# GSMGPSShield.net
KiCad netlist of a schematic drawn in EAGLE
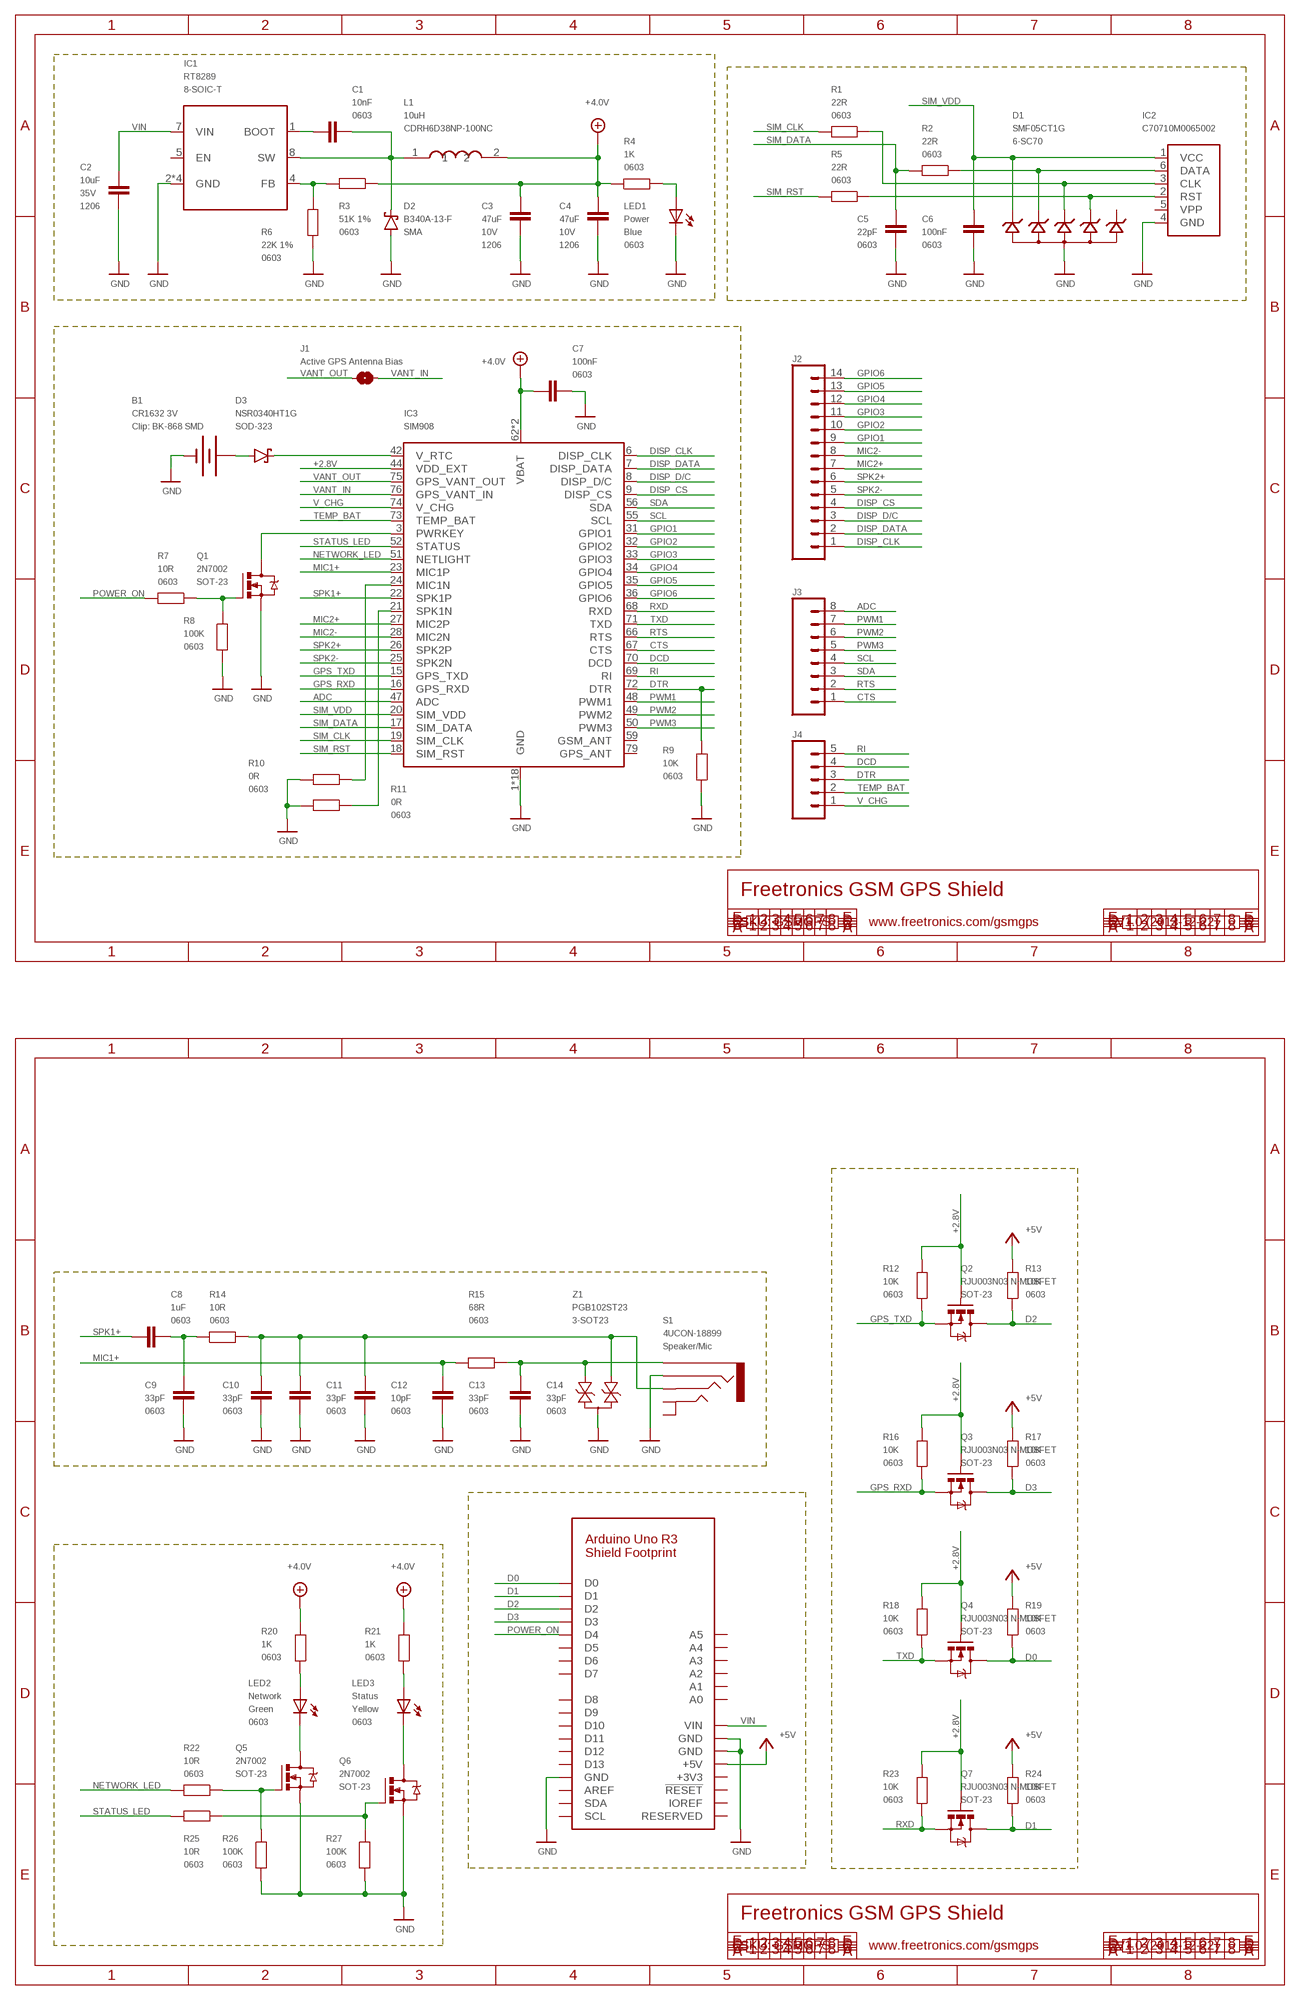
[diagram p0: schematic, sheet 1]

(export (version "E")
  (design (tool "Eeschema 10.0.6"))
  (components
    (comp (ref "B1")
      (value "CR1632 3V")
      (footprint "eagle-import:BATCON_16MM")
      (fields (field (name "FOO") "Clip: BK-868 SMD"))
      (libsource (lib "eagle-import") (part "BATTERY"))
    )
    (comp (ref "C1")
      (value "10nF")
      (footprint "eagle-import:0603")
      (fields (field (name "PACKAGE") "0603"))
      (libsource (lib "eagle-import") (part "CAP0603"))
    )
    (comp (ref "C2")
      (value "10uF")
      (footprint "eagle-import:C1206")
      (fields (field (name "PACKAGE") "1206") (field (name "VOLTAGE") "35V"))
      (libsource (lib "eagle-import") (part "C-EUC1206"))
    )
    (comp (ref "C3")
      (value "47uF")
      (footprint "eagle-import:C1206")
      (fields (field (name "PACKAGE") "1206") (field (name "VOLTAGE") "10V"))
      (libsource (lib "eagle-import") (part "C-EUC1206"))
    )
    (comp (ref "C4")
      (value "47uF")
      (footprint "eagle-import:C1206")
      (fields (field (name "PACKAGE") "1206") (field (name "VOLTAGE") "10V"))
      (libsource (lib "eagle-import") (part "C-EUC1206"))
    )
    (comp (ref "C5")
      (value "22pF")
      (footprint "eagle-import:0603")
      (fields (field (name "PACKAGE") "0603"))
      (libsource (lib "eagle-import") (part "CAP0603"))
    )
    (comp (ref "C6")
      (value "100nF")
      (footprint "eagle-import:0603")
      (fields (field (name "PACKAGE") "0603"))
      (libsource (lib "eagle-import") (part "CAP0603"))
    )
    (comp (ref "C7")
      (value "100nF")
      (footprint "eagle-import:0603")
      (fields (field (name "PACKAGE") "0603"))
      (libsource (lib "eagle-import") (part "CAP0603"))
    )
    (comp (ref "C8")
      (value "1uF")
      (footprint "eagle-import:0603")
      (fields (field (name "PACKAGE") "0603"))
      (libsource (lib "eagle-import") (part "CAP0603"))
    )
    (comp (ref "C9")
      (value "33pF")
      (footprint "eagle-import:0603")
      (fields (field (name "PACKAGE") "0603"))
      (libsource (lib "eagle-import") (part "CAP0603"))
    )
    (comp (ref "C10")
      (value "33pF")
      (footprint "eagle-import:0603")
      (fields (field (name "PACKAGE") "0603"))
      (libsource (lib "eagle-import") (part "CAP0603"))
    )
    (comp (ref "C11")
      (value "33pF")
      (footprint "eagle-import:0603")
      (fields (field (name "PACKAGE") "0603"))
      (libsource (lib "eagle-import") (part "CAP0603"))
    )
    (comp (ref "C12")
      (value "10pF")
      (footprint "eagle-import:0603")
      (fields (field (name "PACKAGE") "0603"))
      (libsource (lib "eagle-import") (part "CAP0603"))
    )
    (comp (ref "C13")
      (value "33pF")
      (footprint "eagle-import:0603")
      (fields (field (name "PACKAGE") "0603"))
      (libsource (lib "eagle-import") (part "CAP0603"))
    )
    (comp (ref "C14")
      (value "33pF")
      (footprint "eagle-import:0603")
      (fields (field (name "PACKAGE") "0603"))
      (libsource (lib "eagle-import") (part "CAP0603"))
    )
    (comp (ref "D1")
      (value "SMF05CT1G")
      (footprint "eagle-import:SC70-6")
      (fields (field (name "PACKAGE") "6-SC70"))
      (libsource (lib "eagle-import") (part "SMF05CT1G"))
    )
    (comp (ref "D2")
      (value "B340A-13-F")
      (footprint "eagle-import:SMA")
      (fields (field (name "PACKAGE") "SMA"))
      (libsource (lib "eagle-import") (part "SCHOTTKY-SMA"))
    )
    (comp (ref "D3")
      (value "NSR0340HT1G")
      (footprint "eagle-import:SOD-323")
      (fields (field (name "PACKAGE") "SOD-323"))
      (libsource (lib "eagle-import") (part "SCHOTTKY-SOD323"))
    )
    (comp (ref "IC1")
      (value "RT8289")
      (footprint "eagle-import:SO08T")
      (fields (field (name "PACKAGE") "8-SOIC-T"))
      (libsource (lib "eagle-import") (part "RT8289"))
    )
    (comp (ref "IC2")
      (value "C70710M0065002")
      (footprint "eagle-import:C70710M0065002")
      (libsource (lib "eagle-import") (part "C70710M0065002"))
    )
    (comp (ref "IC3")
      (value "SIM908")
      (footprint "eagle-import:SIM908")
      (libsource (lib "eagle-import") (part "SIM908"))
    )
    (comp (ref "J1")
      (value "Active GPS Antenna Bias")
      (footprint "eagle-import:SJ")
      (libsource (lib "eagle-import") (part "SJ"))
    )
    (comp (ref "J2")
      (value "M14")
      (footprint "eagle-import:1X14")
      (libsource (lib "eagle-import") (part "M14"))
    )
    (comp (ref "J3")
      (value "M08STD")
      (footprint "eagle-import:1X08")
      (libsource (lib "eagle-import") (part "M08STD"))
    )
    (comp (ref "J4")
      (value "M05PTH")
      (footprint "eagle-import:1X05")
      (libsource (lib "eagle-import") (part "M05PTH"))
    )
    (comp (ref "J5")
      (value "ARDUINO-SHIELD_R3_NOISP")
      (footprint "eagle-import:ARDUINO-SHIELD_R3_NOISP")
      (libsource (lib "eagle-import") (part "ARDUINO-SHIELD_R3_NOISP"))
    )
    (comp (ref "L1")
      (value "10uH")
      (footprint "eagle-import:CDRH")
      (fields (field (name "ID") "CDRH6D38NP-100NC"))
      (libsource (lib "eagle-import") (part "CDRH6D38SMT"))
    )
    (comp (ref "LED1")
      (value "Power")
      (footprint "eagle-import:LED-0603")
      (fields (field (name "COLOR") "Blue") (field (name "PACKAGE") "0603"))
      (libsource (lib "eagle-import") (part "LED0603"))
    )
    (comp (ref "LED2")
      (value "Network")
      (footprint "eagle-import:LED-0603")
      (fields (field (name "COLOR") "Green") (field (name "PACKAGE") "0603"))
      (libsource (lib "eagle-import") (part "LED0603"))
    )
    (comp (ref "LED3")
      (value "Status")
      (footprint "eagle-import:LED-0603")
      (fields (field (name "COLOR") "Yellow") (field (name "PACKAGE") "0603"))
      (libsource (lib "eagle-import") (part "LED0603"))
    )
    (comp (ref "Q1")
      (value "2N7002")
      (footprint "eagle-import:SOT23-3")
      (fields (field (name "PACKAGE") "SOT-23"))
      (libsource (lib "eagle-import") (part "2N7002"))
    )
    (comp (ref "Q2")
      (value "RJU003N03 N-MOSFET")
      (footprint "eagle-import:SOT32-3")
      (fields (field (name "PACKAGE") "SOT-23"))
      (libsource (lib "eagle-import") (part "MOSFET-NSOT-323"))
    )
    (comp (ref "Q3")
      (value "RJU003N03 N-MOSFET")
      (footprint "eagle-import:SOT32-3")
      (fields (field (name "PACKAGE") "SOT-23"))
      (libsource (lib "eagle-import") (part "MOSFET-NSOT-323"))
    )
    (comp (ref "Q4")
      (value "RJU003N03 N-MOSFET")
      (footprint "eagle-import:SOT32-3")
      (fields (field (name "PACKAGE") "SOT-23"))
      (libsource (lib "eagle-import") (part "MOSFET-NSOT-323"))
    )
    (comp (ref "Q5")
      (value "2N7002")
      (footprint "eagle-import:SOT23-3")
      (fields (field (name "PACKAGE") "SOT-23"))
      (libsource (lib "eagle-import") (part "2N7002"))
    )
    (comp (ref "Q6")
      (value "2N7002")
      (footprint "eagle-import:SOT23-3")
      (fields (field (name "PACKAGE") "SOT-23"))
      (libsource (lib "eagle-import") (part "2N7002"))
    )
    (comp (ref "Q7")
      (value "RJU003N03 N-MOSFET")
      (footprint "eagle-import:SOT32-3")
      (fields (field (name "PACKAGE") "SOT-23"))
      (libsource (lib "eagle-import") (part "MOSFET-NSOT-323"))
    )
    (comp (ref "R1")
      (value "22R")
      (footprint "eagle-import:0603")
      (fields (field (name "PACKAGE") "0603"))
      (libsource (lib "eagle-import") (part "RESISTOR0603"))
    )
    (comp (ref "R2")
      (value "22R")
      (footprint "eagle-import:0603")
      (fields (field (name "PACKAGE") "0603"))
      (libsource (lib "eagle-import") (part "RESISTOR0603"))
    )
    (comp (ref "R3")
      (value "51K 1%")
      (footprint "eagle-import:0603")
      (fields (field (name "PACKAGE") "0603"))
      (libsource (lib "eagle-import") (part "RESISTOR0603"))
    )
    (comp (ref "R4")
      (value "1K")
      (footprint "eagle-import:0603")
      (fields (field (name "PACKAGE") "0603"))
      (libsource (lib "eagle-import") (part "RESISTOR0603"))
    )
    (comp (ref "R5")
      (value "22R")
      (footprint "eagle-import:0603")
      (fields (field (name "PACKAGE") "0603"))
      (libsource (lib "eagle-import") (part "RESISTOR0603"))
    )
    (comp (ref "R6")
      (value "22K 1%")
      (footprint "eagle-import:0603")
      (fields (field (name "PACKAGE") "0603"))
      (libsource (lib "eagle-import") (part "RESISTOR0603"))
    )
    (comp (ref "R7")
      (value "10R")
      (footprint "eagle-import:0603")
      (fields (field (name "PACKAGE") "0603"))
      (libsource (lib "eagle-import") (part "RESISTOR0603"))
    )
    (comp (ref "R8")
      (value "100K")
      (footprint "eagle-import:0603")
      (fields (field (name "PACKAGE") "0603"))
      (libsource (lib "eagle-import") (part "RESISTOR0603"))
    )
    (comp (ref "R9")
      (value "10K")
      (footprint "eagle-import:0603")
      (fields (field (name "PACKAGE") "0603"))
      (libsource (lib "eagle-import") (part "RESISTOR0603"))
    )
    (comp (ref "R10")
      (value "0R")
      (footprint "eagle-import:0603")
      (fields (field (name "PACKAGE") "0603"))
      (libsource (lib "eagle-import") (part "RESISTOR0603"))
    )
    (comp (ref "R11")
      (value "0R")
      (footprint "eagle-import:0603")
      (fields (field (name "PACKAGE") "0603"))
      (libsource (lib "eagle-import") (part "RESISTOR0603"))
    )
    (comp (ref "R12")
      (value "10K")
      (footprint "eagle-import:0603")
      (fields (field (name "PACKAGE") "0603"))
      (libsource (lib "eagle-import") (part "RESISTOR0603"))
    )
    (comp (ref "R13")
      (value "10K")
      (footprint "eagle-import:0603")
      (fields (field (name "PACKAGE") "0603"))
      (libsource (lib "eagle-import") (part "RESISTOR0603"))
    )
    (comp (ref "R14")
      (value "10R")
      (footprint "eagle-import:0603")
      (fields (field (name "PACKAGE") "0603"))
      (libsource (lib "eagle-import") (part "RESISTOR0603"))
    )
    (comp (ref "R15")
      (value "68R")
      (footprint "eagle-import:0603")
      (fields (field (name "PACKAGE") "0603"))
      (libsource (lib "eagle-import") (part "RESISTOR0603"))
    )
    (comp (ref "R16")
      (value "10K")
      (footprint "eagle-import:0603")
      (fields (field (name "PACKAGE") "0603"))
      (libsource (lib "eagle-import") (part "RESISTOR0603"))
    )
    (comp (ref "R17")
      (value "10K")
      (footprint "eagle-import:0603")
      (fields (field (name "PACKAGE") "0603"))
      (libsource (lib "eagle-import") (part "RESISTOR0603"))
    )
    (comp (ref "R18")
      (value "10K")
      (footprint "eagle-import:0603")
      (fields (field (name "PACKAGE") "0603"))
      (libsource (lib "eagle-import") (part "RESISTOR0603"))
    )
    (comp (ref "R19")
      (value "10K")
      (footprint "eagle-import:0603")
      (fields (field (name "PACKAGE") "0603"))
      (libsource (lib "eagle-import") (part "RESISTOR0603"))
    )
    (comp (ref "R20")
      (value "1K")
      (footprint "eagle-import:0603")
      (fields (field (name "PACKAGE") "0603"))
      (libsource (lib "eagle-import") (part "RESISTOR0603"))
    )
    (comp (ref "R21")
      (value "1K")
      (footprint "eagle-import:0603")
      (fields (field (name "PACKAGE") "0603"))
      (libsource (lib "eagle-import") (part "RESISTOR0603"))
    )
    (comp (ref "R22")
      (value "10R")
      (footprint "eagle-import:0603")
      (fields (field (name "PACKAGE") "0603"))
      (libsource (lib "eagle-import") (part "RESISTOR0603"))
    )
    (comp (ref "R23")
      (value "10K")
      (footprint "eagle-import:0603")
      (fields (field (name "PACKAGE") "0603"))
      (libsource (lib "eagle-import") (part "RESISTOR0603"))
    )
    (comp (ref "R24")
      (value "10K")
      (footprint "eagle-import:0603")
      (fields (field (name "PACKAGE") "0603"))
      (libsource (lib "eagle-import") (part "RESISTOR0603"))
    )
    (comp (ref "R25")
      (value "10R")
      (footprint "eagle-import:0603")
      (fields (field (name "PACKAGE") "0603"))
      (libsource (lib "eagle-import") (part "RESISTOR0603"))
    )
    (comp (ref "R26")
      (value "100K")
      (footprint "eagle-import:0603")
      (fields (field (name "PACKAGE") "0603"))
      (libsource (lib "eagle-import") (part "RESISTOR0603"))
    )
    (comp (ref "R27")
      (value "100K")
      (footprint "eagle-import:0603")
      (fields (field (name "PACKAGE") "0603"))
      (libsource (lib "eagle-import") (part "RESISTOR0603"))
    )
    (comp (ref "S1")
      (value "4UCON-18899")
      (footprint "eagle-import:4UCON-18899")
      (fields (field (name "FOO") "Speaker/Mic"))
      (libsource (lib "eagle-import") (part "AUDIO-JACK-4POLE"))
    )
    (comp (ref "Z1")
      (value "PGB102ST23")
      (footprint "eagle-import:SOT23-3")
      (fields (field (name "PACKAGE") "3-SOT23"))
      (libsource (lib "eagle-import") (part "PGB102ST23"))
    )
  )
  (nets
    (net (code "1") (name "+4.0V") (class "Default")
      (node (ref "C3") (pin "1") (pinfunction "1_1") (pintype "passive"))
      (node (ref "C4") (pin "1") (pinfunction "1_1") (pintype "passive"))
      (node (ref "C7") (pin "2") (pinfunction "2_2") (pintype "passive"))
      (node (ref "IC3") (pin "62") (pinfunction "VBAT_62") (pintype "bidirectional"))
      (node (ref "IC3") (pin "63") (pinfunction "VBAT_63") (pintype "bidirectional"))
      (node (ref "L1") (pin "2") (pinfunction "2_2") (pintype "bidirectional"))
      (node (ref "R20") (pin "1") (pinfunction "1_1") (pintype "passive"))
      (node (ref "R21") (pin "1") (pinfunction "1_1") (pintype "passive"))
      (node (ref "R3") (pin "1") (pinfunction "1_1") (pintype "passive"))
      (node (ref "R4") (pin "1") (pinfunction "1_1") (pintype "passive"))
    )
    (net (code "2") (name "+5V") (class "Default")
      (node (ref "J5") (pin "+5V") (pinfunction "+5V_+5V") (pintype "power_in"))
      (node (ref "R13") (pin "1") (pinfunction "1_1") (pintype "passive"))
      (node (ref "R17") (pin "1") (pinfunction "1_1") (pintype "passive"))
      (node (ref "R19") (pin "1") (pinfunction "1_1") (pintype "passive"))
      (node (ref "R24") (pin "1") (pinfunction "1_1") (pintype "passive"))
    )
    (net (code "3") (name "/+2.8V") (class "Default")
      (node (ref "IC3") (pin "44") (pinfunction "VDD_EXT_44") (pintype "bidirectional"))
      (node (ref "Q2") (pin "1") (pinfunction "G_1") (pintype "passive"))
      (node (ref "Q3") (pin "1") (pinfunction "G_1") (pintype "passive"))
      (node (ref "Q4") (pin "1") (pinfunction "G_1") (pintype "passive"))
      (node (ref "Q7") (pin "1") (pinfunction "G_1") (pintype "passive"))
      (node (ref "R12") (pin "1") (pinfunction "1_1") (pintype "passive"))
      (node (ref "R16") (pin "1") (pinfunction "1_1") (pintype "passive"))
      (node (ref "R18") (pin "1") (pinfunction "1_1") (pintype "passive"))
      (node (ref "R23") (pin "1") (pinfunction "1_1") (pintype "passive"))
    )
    (net (code "4") (name "/+3V3") (class "Default")
      (node (ref "J5") (pin "3V3") (pinfunction "+3V3_3V3") (pintype "power_in"))
    )
    (net (code "5") (name "/ADC") (class "Default")
      (node (ref "IC3") (pin "47") (pinfunction "ADC_47") (pintype "bidirectional"))
      (node (ref "J3") (pin "8") (pinfunction "8_8") (pintype "passive"))
    )
    (net (code "6") (name "/CTS") (class "Default")
      (node (ref "IC3") (pin "67") (pinfunction "CTS_67") (pintype "bidirectional"))
      (node (ref "J3") (pin "1") (pinfunction "1_1") (pintype "passive"))
    )
    (net (code "7") (name "/D0") (class "Default")
      (node (ref "J5") (pin "D0") (pinfunction "D0_D0") (pintype "bidirectional"))
      (node (ref "Q4") (pin "3") (pinfunction "D_3") (pintype "passive"))
      (node (ref "R19") (pin "2") (pinfunction "2_2") (pintype "passive"))
    )
    (net (code "8") (name "/D1") (class "Default")
      (node (ref "J5") (pin "D1") (pinfunction "D1_D1") (pintype "bidirectional"))
      (node (ref "Q7") (pin "3") (pinfunction "D_3") (pintype "passive"))
      (node (ref "R24") (pin "2") (pinfunction "2_2") (pintype "passive"))
    )
    (net (code "9") (name "/D2") (class "Default")
      (node (ref "J5") (pin "D2") (pinfunction "D2_D2") (pintype "bidirectional"))
      (node (ref "Q2") (pin "3") (pinfunction "D_3") (pintype "passive"))
      (node (ref "R13") (pin "2") (pinfunction "2_2") (pintype "passive"))
    )
    (net (code "10") (name "/D3") (class "Default")
      (node (ref "J5") (pin "D3") (pinfunction "D3_D3") (pintype "bidirectional"))
      (node (ref "Q3") (pin "3") (pinfunction "D_3") (pintype "passive"))
      (node (ref "R17") (pin "2") (pinfunction "2_2") (pintype "passive"))
    )
    (net (code "11") (name "/DCD") (class "Default")
      (node (ref "IC3") (pin "70") (pinfunction "DCD_70") (pintype "bidirectional"))
      (node (ref "J4") (pin "4") (pinfunction "4_4") (pintype "passive"))
    )
    (net (code "12") (name "/DISP_CLK") (class "Default")
      (node (ref "IC3") (pin "6") (pinfunction "DISP_CLK_6") (pintype "bidirectional"))
      (node (ref "J2") (pin "1") (pinfunction "1_1") (pintype "passive"))
    )
    (net (code "13") (name "/DISP_CS") (class "Default")
      (node (ref "IC3") (pin "9") (pinfunction "DISP_CS_9") (pintype "bidirectional"))
      (node (ref "J2") (pin "4") (pinfunction "4_4") (pintype "passive"))
    )
    (net (code "14") (name "/DISP_DATA") (class "Default")
      (node (ref "IC3") (pin "7") (pinfunction "DISP_DATA_7") (pintype "bidirectional"))
      (node (ref "J2") (pin "2") (pinfunction "2_2") (pintype "passive"))
    )
    (net (code "15") (name "/DISP_D{slash}C") (class "Default")
      (node (ref "IC3") (pin "8") (pinfunction "DISP_D/C_8") (pintype "bidirectional"))
      (node (ref "J2") (pin "3") (pinfunction "3_3") (pintype "passive"))
    )
    (net (code "16") (name "/DTR") (class "Default")
      (node (ref "IC3") (pin "72") (pinfunction "DTR_72") (pintype "bidirectional"))
      (node (ref "J4") (pin "3") (pinfunction "3_3") (pintype "passive"))
      (node (ref "R9") (pin "1") (pinfunction "1_1") (pintype "passive"))
    )
    (net (code "17") (name "/GPIO1") (class "Default")
      (node (ref "IC3") (pin "31") (pinfunction "GPIO1_31") (pintype "bidirectional"))
      (node (ref "J2") (pin "9") (pinfunction "9_9") (pintype "passive"))
    )
    (net (code "18") (name "/GPIO2") (class "Default")
      (node (ref "IC3") (pin "32") (pinfunction "GPIO2_32") (pintype "bidirectional"))
      (node (ref "J2") (pin "10") (pinfunction "10_10") (pintype "passive"))
    )
    (net (code "19") (name "/GPIO3") (class "Default")
      (node (ref "IC3") (pin "33") (pinfunction "GPIO3_33") (pintype "bidirectional"))
      (node (ref "J2") (pin "11") (pinfunction "11_11") (pintype "passive"))
    )
    (net (code "20") (name "/GPIO4") (class "Default")
      (node (ref "IC3") (pin "34") (pinfunction "GPIO4_34") (pintype "bidirectional"))
      (node (ref "J2") (pin "12") (pinfunction "12_12") (pintype "passive"))
    )
    (net (code "21") (name "/GPIO5") (class "Default")
      (node (ref "IC3") (pin "35") (pinfunction "GPIO5_35") (pintype "bidirectional"))
      (node (ref "J2") (pin "13") (pinfunction "13_13") (pintype "passive"))
    )
    (net (code "22") (name "/GPIO6") (class "Default")
      (node (ref "IC3") (pin "36") (pinfunction "GPIO6_36") (pintype "bidirectional"))
      (node (ref "J2") (pin "14") (pinfunction "14_14") (pintype "passive"))
    )
    (net (code "23") (name "/GPS_RXD") (class "Default")
      (node (ref "IC3") (pin "16") (pinfunction "GPS_RXD_16") (pintype "bidirectional"))
      (node (ref "Q3") (pin "2") (pinfunction "S_2") (pintype "passive"))
      (node (ref "R16") (pin "2") (pinfunction "2_2") (pintype "passive"))
    )
    (net (code "24") (name "/GPS_TXD") (class "Default")
      (node (ref "IC3") (pin "15") (pinfunction "GPS_TXD_15") (pintype "bidirectional"))
      (node (ref "Q2") (pin "2") (pinfunction "S_2") (pintype "passive"))
      (node (ref "R12") (pin "2") (pinfunction "2_2") (pintype "passive"))
    )
    (net (code "25") (name "/MIC1+") (class "Default")
      (node (ref "C13") (pin "2") (pinfunction "2_2") (pintype "passive"))
      (node (ref "IC3") (pin "23") (pinfunction "MIC1P_23") (pintype "bidirectional"))
      (node (ref "R15") (pin "1") (pinfunction "1_1") (pintype "passive"))
    )
    (net (code "26") (name "/MIC2+") (class "Default")
      (node (ref "IC3") (pin "27") (pinfunction "MIC2P_27") (pintype "bidirectional"))
      (node (ref "J2") (pin "7") (pinfunction "7_7") (pintype "passive"))
    )
    (net (code "27") (name "/MIC2-") (class "Default")
      (node (ref "IC3") (pin "28") (pinfunction "MIC2N_28") (pintype "bidirectional"))
      (node (ref "J2") (pin "8") (pinfunction "8_8") (pintype "passive"))
    )
    (net (code "28") (name "/NETWORK_LED") (class "Default")
      (node (ref "IC3") (pin "51") (pinfunction "NETLIGHT_51") (pintype "bidirectional"))
      (node (ref "R22") (pin "2") (pinfunction "2_2") (pintype "passive"))
    )
    (net (code "29") (name "/POWER_ON") (class "Default")
      (node (ref "J5") (pin "D4") (pinfunction "D4_D4") (pintype "bidirectional"))
      (node (ref "R7") (pin "2") (pinfunction "2_2") (pintype "passive"))
    )
    (net (code "30") (name "/PWM1") (class "Default")
      (node (ref "IC3") (pin "48") (pinfunction "PWM1_48") (pintype "bidirectional"))
      (node (ref "J3") (pin "7") (pinfunction "7_7") (pintype "passive"))
    )
    (net (code "31") (name "/PWM2") (class "Default")
      (node (ref "IC3") (pin "49") (pinfunction "PWM2_49") (pintype "bidirectional"))
      (node (ref "J3") (pin "6") (pinfunction "6_6") (pintype "passive"))
    )
    (net (code "32") (name "/PWM3") (class "Default")
      (node (ref "IC3") (pin "50") (pinfunction "PWM3_50") (pintype "bidirectional"))
      (node (ref "J3") (pin "5") (pinfunction "5_5") (pintype "passive"))
    )
    (net (code "33") (name "/RI") (class "Default")
      (node (ref "IC3") (pin "69") (pinfunction "RI_69") (pintype "bidirectional"))
      (node (ref "J4") (pin "5") (pinfunction "5_5") (pintype "passive"))
    )
    (net (code "34") (name "/RTS") (class "Default")
      (node (ref "IC3") (pin "66") (pinfunction "RTS_66") (pintype "bidirectional"))
      (node (ref "J3") (pin "2") (pinfunction "2_2") (pintype "passive"))
    )
    (net (code "35") (name "/RXD") (class "Default")
      (node (ref "IC3") (pin "68") (pinfunction "RXD_68") (pintype "bidirectional"))
      (node (ref "Q7") (pin "2") (pinfunction "S_2") (pintype "passive"))
      (node (ref "R23") (pin "2") (pinfunction "2_2") (pintype "passive"))
    )
    (net (code "36") (name "/SCL") (class "Default")
      (node (ref "IC3") (pin "55") (pinfunction "SCL_55") (pintype "bidirectional"))
      (node (ref "J3") (pin "4") (pinfunction "4_4") (pintype "passive"))
    )
    (net (code "37") (name "/SDA") (class "Default")
      (node (ref "IC3") (pin "56") (pinfunction "SDA_56") (pintype "bidirectional"))
      (node (ref "J3") (pin "3") (pinfunction "3_3") (pintype "passive"))
    )
    (net (code "38") (name "/SIM_CLK") (class "Default")
      (node (ref "IC3") (pin "19") (pinfunction "SIM_CLK_19") (pintype "bidirectional"))
      (node (ref "R1") (pin "2") (pinfunction "2_2") (pintype "passive"))
    )
    (net (code "39") (name "/SIM_DATA") (class "Default")
      (node (ref "C5") (pin "2") (pinfunction "2_2") (pintype "passive"))
      (node (ref "IC3") (pin "17") (pinfunction "SIM_DATA_17") (pintype "bidirectional"))
      (node (ref "R2") (pin "2") (pinfunction "2_2") (pintype "passive"))
    )
    (net (code "40") (name "/SIM_RST") (class "Default")
      (node (ref "IC3") (pin "18") (pinfunction "SIM_RST_18") (pintype "bidirectional"))
      (node (ref "R5") (pin "2") (pinfunction "2_2") (pintype "passive"))
    )
    (net (code "41") (name "/SIM_VDD") (class "Default")
      (node (ref "C6") (pin "2") (pinfunction "2_2") (pintype "passive"))
      (node (ref "D1") (pin "1") (pinfunction "K1_1") (pintype "bidirectional"))
      (node (ref "IC2") (pin "1") (pinfunction "VCC_1") (pintype "bidirectional"))
      (node (ref "IC3") (pin "20") (pinfunction "SIM_VDD_20") (pintype "bidirectional"))
    )
    (net (code "42") (name "/SPK1+") (class "Default")
      (node (ref "C8") (pin "2") (pinfunction "2_2") (pintype "passive"))
      (node (ref "IC3") (pin "22") (pinfunction "SPK1P_22") (pintype "bidirectional"))
    )
    (net (code "43") (name "/SPK2+") (class "Default")
      (node (ref "IC3") (pin "26") (pinfunction "SPK2P_26") (pintype "bidirectional"))
      (node (ref "J2") (pin "6") (pinfunction "6_6") (pintype "passive"))
    )
    (net (code "44") (name "/SPK2-") (class "Default")
      (node (ref "IC3") (pin "25") (pinfunction "SPK2N_25") (pintype "bidirectional"))
      (node (ref "J2") (pin "5") (pinfunction "5_5") (pintype "passive"))
    )
    (net (code "45") (name "/STATUS_LED") (class "Default")
      (node (ref "IC3") (pin "52") (pinfunction "STATUS_52") (pintype "bidirectional"))
      (node (ref "R25") (pin "2") (pinfunction "2_2") (pintype "passive"))
    )
    (net (code "46") (name "/TEMP_BAT") (class "Default")
      (node (ref "IC3") (pin "73") (pinfunction "TEMP_BAT_73") (pintype "bidirectional"))
      (node (ref "J4") (pin "2") (pinfunction "2_2") (pintype "passive"))
    )
    (net (code "47") (name "/TXD") (class "Default")
      (node (ref "IC3") (pin "71") (pinfunction "TXD_71") (pintype "bidirectional"))
      (node (ref "Q4") (pin "2") (pinfunction "S_2") (pintype "passive"))
      (node (ref "R18") (pin "2") (pinfunction "2_2") (pintype "passive"))
    )
    (net (code "48") (name "/VANT_IN") (class "Default")
      (node (ref "IC3") (pin "76") (pinfunction "GPS_VANT_IN_76") (pintype "bidirectional"))
      (node (ref "J1") (pin "2") (pinfunction "2_2") (pintype "passive"))
    )
    (net (code "49") (name "/VANT_OUT") (class "Default")
      (node (ref "IC3") (pin "75") (pinfunction "GPS_VANT_OUT_75") (pintype "bidirectional"))
      (node (ref "J1") (pin "1") (pinfunction "1_1") (pintype "passive"))
    )
    (net (code "50") (name "/VIN") (class "Default")
      (node (ref "C2") (pin "1") (pinfunction "1_1") (pintype "passive"))
      (node (ref "IC1") (pin "7") (pinfunction "VIN_7") (pintype "bidirectional"))
      (node (ref "J5") (pin "VIN") (pinfunction "VIN_VIN") (pintype "power_in"))
    )
    (net (code "51") (name "/V_CHG") (class "Default")
      (node (ref "IC3") (pin "74") (pinfunction "V_CHG_74") (pintype "bidirectional"))
      (node (ref "J4") (pin "1") (pinfunction "1_1") (pintype "passive"))
    )
    (net (code "52") (name "GND") (class "Default")
      (node (ref "B1") (pin "GND") (pinfunction "-_GND") (pintype "power_in"))
      (node (ref "C10") (pin "1") (pinfunction "1_1") (pintype "passive"))
      (node (ref "C11") (pin "1") (pinfunction "1_1") (pintype "passive"))
      (node (ref "C12") (pin "1") (pinfunction "1_1") (pintype "passive"))
      (node (ref "C13") (pin "1") (pinfunction "1_1") (pintype "passive"))
      (node (ref "C14") (pin "1") (pinfunction "1_1") (pintype "passive"))
      (node (ref "C2") (pin "2") (pinfunction "2_2") (pintype "passive"))
      (node (ref "C3") (pin "2") (pinfunction "2_2") (pintype "passive"))
      (node (ref "C4") (pin "2") (pinfunction "2_2") (pintype "passive"))
      (node (ref "C5") (pin "1") (pinfunction "1_1") (pintype "passive"))
      (node (ref "C6") (pin "1") (pinfunction "1_1") (pintype "passive"))
      (node (ref "C7") (pin "1") (pinfunction "1_1") (pintype "passive"))
      (node (ref "C9") (pin "1") (pinfunction "1_1") (pintype "passive"))
      (node (ref "D1") (pin "2") (pinfunction "A2_2") (pintype "bidirectional"))
      (node (ref "D2") (pin "A") (pinfunction "A_A") (pintype "passive"))
      (node (ref "IC1") (pin "2") (pinfunction "GND_2") (pintype "bidirectional"))
      (node (ref "IC1") (pin "3") (pinfunction "GND_3") (pintype "bidirectional"))
      (node (ref "IC1") (pin "6") (pinfunction "GND_6") (pintype "bidirectional"))
      (node (ref "IC1") (pin "PAD") (pinfunction "GND_PAD") (pintype "bidirectional"))
      (node (ref "IC2") (pin "4") (pinfunction "GND_4") (pintype "bidirectional"))
      (node (ref "IC3") (pin "1") (pinfunction "GND_1") (pintype "bidirectional"))
      (node (ref "IC3") (pin "10") (pinfunction "GND_10") (pintype "bidirectional"))
      (node (ref "IC3") (pin "14") (pinfunction "GND_14") (pintype "bidirectional"))
      (node (ref "IC3") (pin "2") (pinfunction "GND_2") (pintype "bidirectional"))
      (node (ref "IC3") (pin "37") (pinfunction "GND_37") (pintype "bidirectional"))
      (node (ref "IC3") (pin "40") (pinfunction "GND_40") (pintype "bidirectional"))
      (node (ref "IC3") (pin "41") (pinfunction "GND_41") (pintype "bidirectional"))
      (node (ref "IC3") (pin "43") (pinfunction "GND_43") (pintype "bidirectional"))
      (node (ref "IC3") (pin "5") (pinfunction "GND_5") (pintype "bidirectional"))
      (node (ref "IC3") (pin "57") (pinfunction "GND_57") (pintype "bidirectional"))
      (node (ref "IC3") (pin "58") (pinfunction "GND_58") (pintype "bidirectional"))
      (node (ref "IC3") (pin "60") (pinfunction "GND_60") (pintype "bidirectional"))
      (node (ref "IC3") (pin "61") (pinfunction "GND_61") (pintype "bidirectional"))
      (node (ref "IC3") (pin "64") (pinfunction "GND_64") (pintype "bidirectional"))
      (node (ref "IC3") (pin "65") (pinfunction "GND_65") (pintype "bidirectional"))
      (node (ref "IC3") (pin "77") (pinfunction "GND_77") (pintype "bidirectional"))
      (node (ref "IC3") (pin "78") (pinfunction "GND_78") (pintype "bidirectional"))
      (node (ref "IC3") (pin "80") (pinfunction "GND_80") (pintype "bidirectional"))
      (node (ref "J5") (pin "GND") (pinfunction "GND_GND") (pintype "power_in"))
      (node (ref "J5") (pin "GND@0") (pinfunction "GND_GND@0") (pintype "power_in"))
      (node (ref "J5") (pin "GND@1") (pinfunction "GND_GND@1") (pintype "power_in"))
      (node (ref "LED1") (pin "C") (pinfunction "C_C") (pintype "passive"))
      (node (ref "Q1") (pin "2") (pinfunction "S_2") (pintype "passive"))
      (node (ref "Q5") (pin "2") (pinfunction "S_2") (pintype "passive"))
      (node (ref "Q6") (pin "2") (pinfunction "S_2") (pintype "passive"))
      (node (ref "R10") (pin "2") (pinfunction "2_2") (pintype "passive"))
      (node (ref "R11") (pin "2") (pinfunction "2_2") (pintype "passive"))
      (node (ref "R26") (pin "1") (pinfunction "1_1") (pintype "passive"))
      (node (ref "R27") (pin "1") (pinfunction "1_1") (pintype "passive"))
      (node (ref "R6") (pin "1") (pinfunction "1_1") (pintype "passive"))
      (node (ref "R8") (pin "1") (pinfunction "1_1") (pintype "passive"))
      (node (ref "R9") (pin "2") (pinfunction "2_2") (pintype "passive"))
      (node (ref "S1") (pin "4") (pinfunction "4_4") (pintype "bidirectional"))
      (node (ref "Z1") (pin "3") (pinfunction "P$3_3") (pintype "bidirectional"))
    )
    (net (code "53") (name "Net-(B1-+)") (class "Default")
      (node (ref "B1") (pin "PWR@1") (pinfunction "+_PWR@1") (pintype "power_in"))
      (node (ref "D3") (pin "A") (pinfunction "A_A") (pintype "passive"))
    )
    (net (code "54") (name "Net-(C8-Pad1)") (class "Default")
      (node (ref "C8") (pin "1") (pinfunction "1_1") (pintype "passive"))
      (node (ref "C9") (pin "2") (pinfunction "2_2") (pintype "passive"))
      (node (ref "R14") (pin "1") (pinfunction "1_1") (pintype "passive"))
    )
    (net (code "55") (name "Net-(D1-K3)") (class "Default")
      (node (ref "D1") (pin "3") (pinfunction "K3_3") (pintype "bidirectional"))
      (node (ref "IC2") (pin "6") (pinfunction "DATA_6") (pintype "bidirectional"))
      (node (ref "R2") (pin "1") (pinfunction "1_1") (pintype "passive"))
    )
    (net (code "56") (name "Net-(D1-K4)") (class "Default")
      (node (ref "D1") (pin "4") (pinfunction "K4_4") (pintype "bidirectional"))
      (node (ref "IC2") (pin "3") (pinfunction "CLK_3") (pintype "bidirectional"))
      (node (ref "R1") (pin "1") (pinfunction "1_1") (pintype "passive"))
    )
    (net (code "57") (name "Net-(D1-K5)") (class "Default")
      (node (ref "D1") (pin "5") (pinfunction "K5_5") (pintype "bidirectional"))
      (node (ref "IC2") (pin "2") (pinfunction "RST_2") (pintype "bidirectional"))
      (node (ref "R5") (pin "1") (pinfunction "1_1") (pintype "passive"))
    )
    (net (code "58") (name "Net-(IC1-BOOT)") (class "Default")
      (node (ref "C1") (pin "2") (pinfunction "2_2") (pintype "passive"))
      (node (ref "IC1") (pin "1") (pinfunction "BOOT_1") (pintype "bidirectional"))
    )
    (net (code "59") (name "Net-(IC1-FB)") (class "Default")
      (node (ref "IC1") (pin "4") (pinfunction "FB_4") (pintype "bidirectional"))
      (node (ref "R3") (pin "2") (pinfunction "2_2") (pintype "passive"))
      (node (ref "R6") (pin "2") (pinfunction "2_2") (pintype "passive"))
    )
    (net (code "60") (name "Net-(IC1-SW)") (class "Default")
      (node (ref "C1") (pin "1") (pinfunction "1_1") (pintype "passive"))
      (node (ref "D2") (pin "K") (pinfunction "K_K") (pintype "passive"))
      (node (ref "IC1") (pin "8") (pinfunction "SW_8") (pintype "bidirectional"))
      (node (ref "L1") (pin "1") (pinfunction "1_1") (pintype "bidirectional"))
    )
    (net (code "61") (name "Net-(IC3-MIC1N)") (class "Default")
      (node (ref "IC3") (pin "24") (pinfunction "MIC1N_24") (pintype "bidirectional"))
      (node (ref "R10") (pin "1") (pinfunction "1_1") (pintype "passive"))
    )
    (net (code "62") (name "Net-(IC3-PWRKEY)") (class "Default")
      (node (ref "IC3") (pin "3") (pinfunction "PWRKEY_3") (pintype "bidirectional"))
      (node (ref "Q1") (pin "3") (pinfunction "D_3") (pintype "passive"))
    )
    (net (code "63") (name "Net-(IC3-SPK1N)") (class "Default")
      (node (ref "IC3") (pin "21") (pinfunction "SPK1N_21") (pintype "bidirectional"))
      (node (ref "R11") (pin "1") (pinfunction "1_1") (pintype "passive"))
    )
    (net (code "64") (name "Net-(IC3-V_RTC)") (class "Default")
      (node (ref "D3") (pin "K") (pinfunction "K_K") (pintype "passive"))
      (node (ref "IC3") (pin "42") (pinfunction "V_RTC_42") (pintype "bidirectional"))
    )
    (net (code "65") (name "Net-(LED1-PadA)") (class "Default")
      (node (ref "LED1") (pin "A") (pinfunction "A_A") (pintype "passive"))
      (node (ref "R4") (pin "2") (pinfunction "2_2") (pintype "passive"))
    )
    (net (code "66") (name "Net-(LED2-PadA)") (class "Default")
      (node (ref "LED2") (pin "A") (pinfunction "A_A") (pintype "passive"))
      (node (ref "R20") (pin "2") (pinfunction "2_2") (pintype "passive"))
    )
    (net (code "67") (name "Net-(LED3-PadA)") (class "Default")
      (node (ref "LED3") (pin "A") (pinfunction "A_A") (pintype "passive"))
      (node (ref "R21") (pin "2") (pinfunction "2_2") (pintype "passive"))
    )
    (net (code "68") (name "Net-(Q1-G)") (class "Default")
      (node (ref "Q1") (pin "1") (pinfunction "G_1") (pintype "passive"))
      (node (ref "R7") (pin "1") (pinfunction "1_1") (pintype "passive"))
      (node (ref "R8") (pin "2") (pinfunction "2_2") (pintype "passive"))
    )
    (net (code "69") (name "Net-(Q5-D)") (class "Default")
      (node (ref "LED2") (pin "C") (pinfunction "C_C") (pintype "passive"))
      (node (ref "Q5") (pin "3") (pinfunction "D_3") (pintype "passive"))
    )
    (net (code "70") (name "Net-(Q5-G)") (class "Default")
      (node (ref "Q5") (pin "1") (pinfunction "G_1") (pintype "passive"))
      (node (ref "R22") (pin "1") (pinfunction "1_1") (pintype "passive"))
      (node (ref "R26") (pin "2") (pinfunction "2_2") (pintype "passive"))
    )
    (net (code "71") (name "Net-(Q6-D)") (class "Default")
      (node (ref "LED3") (pin "C") (pinfunction "C_C") (pintype "passive"))
      (node (ref "Q6") (pin "3") (pinfunction "D_3") (pintype "passive"))
    )
    (net (code "72") (name "Net-(Q6-G)") (class "Default")
      (node (ref "Q6") (pin "1") (pinfunction "G_1") (pintype "passive"))
      (node (ref "R25") (pin "1") (pinfunction "1_1") (pintype "passive"))
      (node (ref "R27") (pin "2") (pinfunction "2_2") (pintype "passive"))
    )
    (net (code "73") (name "Net-(Z1-P$1)") (class "Default")
      (node (ref "C10") (pin "2") (pinfunction "2_2") (pintype "passive"))
      (node (ref "C11") (pin "2") (pinfunction "2_2") (pintype "passive"))
      (node (ref "C12") (pin "2") (pinfunction "2_2") (pintype "passive"))
      (node (ref "R14") (pin "2") (pinfunction "2_2") (pintype "passive"))
      (node (ref "S1") (pin "3") (pinfunction "3_3") (pintype "bidirectional"))
      (node (ref "Z1") (pin "1") (pinfunction "P$1_1") (pintype "bidirectional"))
    )
    (net (code "74") (name "Net-(Z1-P$2)") (class "Default")
      (node (ref "C14") (pin "2") (pinfunction "2_2") (pintype "passive"))
      (node (ref "R15") (pin "2") (pinfunction "2_2") (pintype "passive"))
      (node (ref "S1") (pin "1") (pinfunction "1_1") (pintype "bidirectional"))
      (node (ref "Z1") (pin "2") (pinfunction "P$2_2") (pintype "bidirectional"))
    )
    (net (code "75") (name "unconnected-(D1-K6-Pad6)") (class "Default")
      (node (ref "D1") (pin "6") (pinfunction "K6_6") (pintype "bidirectional"))
    )
    (net (code "76") (name "unconnected-(IC1-EN-Pad5)") (class "Default")
      (node (ref "IC1") (pin "5") (pinfunction "EN_5") (pintype "bidirectional"))
    )
    (net (code "77") (name "unconnected-(IC2-VPP-Pad5)") (class "Default")
      (node (ref "IC2") (pin "5") (pinfunction "VPP_5") (pintype "bidirectional"))
    )
    (net (code "78") (name "unconnected-(IC3-GPS_ANT-Pad79)") (class "Default")
      (node (ref "IC3") (pin "79") (pinfunction "GPS_ANT_79") (pintype "bidirectional"))
    )
    (net (code "79") (name "unconnected-(IC3-GSM_ANT-Pad59)") (class "Default")
      (node (ref "IC3") (pin "59") (pinfunction "GSM_ANT_59") (pintype "bidirectional"))
    )
    (net (code "80") (name "unconnected-(J5-PadA0)") (class "Default")
      (node (ref "J5") (pin "A0") (pinfunction "A0_A0") (pintype "bidirectional"))
    )
    (net (code "81") (name "unconnected-(J5-PadA1)") (class "Default")
      (node (ref "J5") (pin "A1") (pinfunction "A1_A1") (pintype "bidirectional"))
    )
    (net (code "82") (name "unconnected-(J5-PadA2)") (class "Default")
      (node (ref "J5") (pin "A2") (pinfunction "A2_A2") (pintype "bidirectional"))
    )
    (net (code "83") (name "unconnected-(J5-PadA3)") (class "Default")
      (node (ref "J5") (pin "A3") (pinfunction "A3_A3") (pintype "bidirectional"))
    )
    (net (code "84") (name "unconnected-(J5-PadA4)") (class "Default")
      (node (ref "J5") (pin "A4") (pinfunction "A4_A4") (pintype "bidirectional"))
    )
    (net (code "85") (name "unconnected-(J5-PadA5)") (class "Default")
      (node (ref "J5") (pin "A5") (pinfunction "A5_A5") (pintype "bidirectional"))
    )
    (net (code "86") (name "unconnected-(J5-PadAREF)") (class "Default")
      (node (ref "J5") (pin "AREF") (pinfunction "AREF_AREF") (pintype "bidirectional"))
    )
    (net (code "87") (name "unconnected-(J5-PadD5)") (class "Default")
      (node (ref "J5") (pin "D5") (pinfunction "D5_D5") (pintype "bidirectional"))
    )
    (net (code "88") (name "unconnected-(J5-PadD6)") (class "Default")
      (node (ref "J5") (pin "D6") (pinfunction "D6_D6") (pintype "bidirectional"))
    )
    (net (code "89") (name "unconnected-(J5-PadD7)") (class "Default")
      (node (ref "J5") (pin "D7") (pinfunction "D7_D7") (pintype "bidirectional"))
    )
    (net (code "90") (name "unconnected-(J5-PadD8)") (class "Default")
      (node (ref "J5") (pin "D8") (pinfunction "D8_D8") (pintype "bidirectional"))
    )
    (net (code "91") (name "unconnected-(J5-PadD9)") (class "Default")
      (node (ref "J5") (pin "D9") (pinfunction "D9_D9") (pintype "bidirectional"))
    )
    (net (code "92") (name "unconnected-(J5-PadD10)") (class "Default")
      (node (ref "J5") (pin "D10") (pinfunction "D10_D10") (pintype "bidirectional"))
    )
    (net (code "93") (name "unconnected-(J5-PadD11)") (class "Default")
      (node (ref "J5") (pin "D11") (pinfunction "D11_D11") (pintype "bidirectional"))
    )
    (net (code "94") (name "unconnected-(J5-PadD12)") (class "Default")
      (node (ref "J5") (pin "D12") (pinfunction "D12_D12") (pintype "bidirectional"))
    )
    (net (code "95") (name "unconnected-(J5-PadD13)") (class "Default")
      (node (ref "J5") (pin "D13") (pinfunction "D13_D13") (pintype "bidirectional"))
    )
    (net (code "96") (name "unconnected-(J5-PadIOREF)") (class "Default")
      (node (ref "J5") (pin "IOREF") (pinfunction "IOREF_IOREF") (pintype "output"))
    )
    (net (code "97") (name "unconnected-(J5-PadRESERVED)") (class "Default")
      (node (ref "J5") (pin "RESERVED") (pinfunction "RESERVED_RESERVED") (pintype "no_connect"))
    )
    (net (code "98") (name "unconnected-(J5-PadSCL)") (class "Default")
      (node (ref "J5") (pin "SCL") (pinfunction "SCL_SCL") (pintype "bidirectional"))
    )
    (net (code "99") (name "unconnected-(J5-PadSDA)") (class "Default")
      (node (ref "J5") (pin "SDA") (pinfunction "SDA_SDA") (pintype "bidirectional"))
    )
    (net (code "100") (name "unconnected-(J5-~{RESET}-Pad!RESET)") (class "Default")
      (node (ref "J5") (pin "!RESET") (pinfunction "~{RESET}_!RESET") (pintype "bidirectional"))
    )
    (net (code "101") (name "unconnected-(S1-Pad2A)") (class "Default")
      (node (ref "S1") (pin "2A") (pinfunction "2A_2A") (pintype "bidirectional"))
    )
    (net (code "102") (name "unconnected-(S1-Pad2B)") (class "Default")
      (node (ref "S1") (pin "2B") (pinfunction "2B_2B") (pintype "bidirectional"))
    )
  )
)
